# MMC_2_2_PSU.net
KiCad netlist of a schematic drawn in Altium Designer
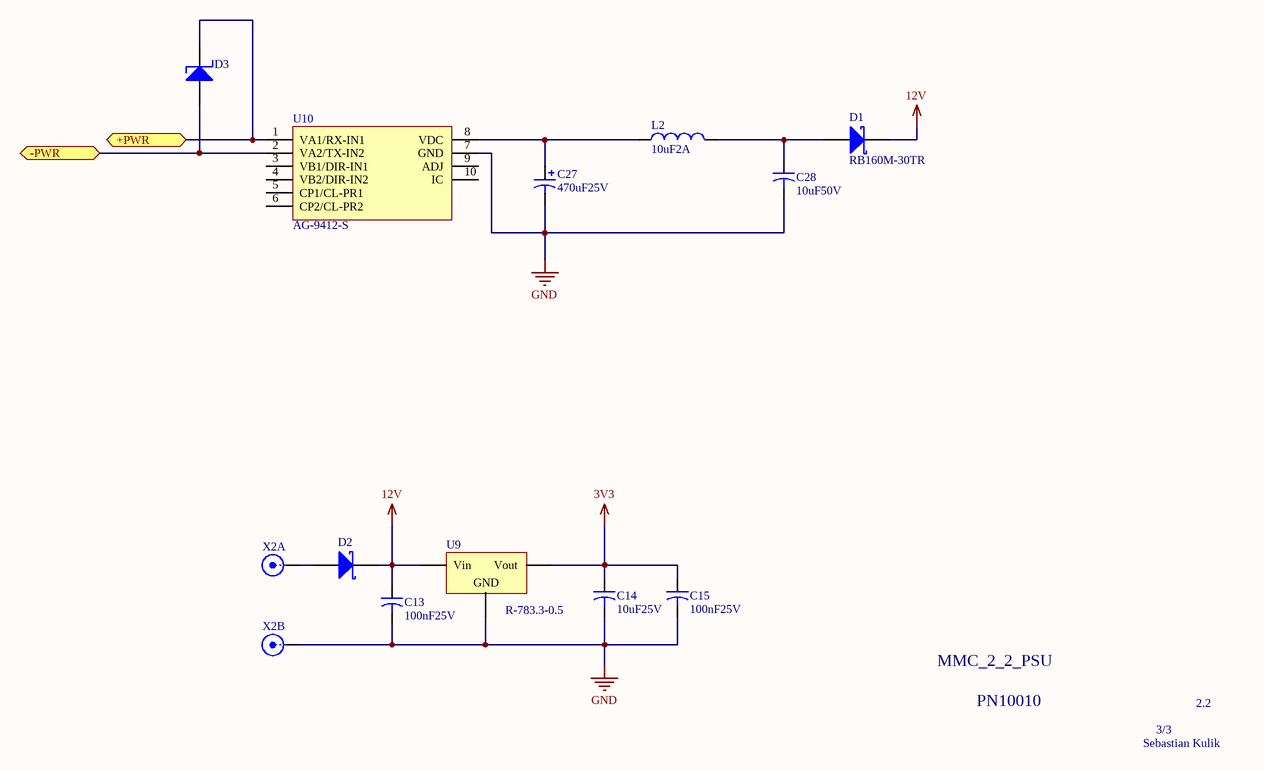
[diagram p0: MMC_2_2_PSU.SchDoc]

(export (version "E")
  (design (tool "Eeschema 10.0.6"))
  (components
    (comp (ref "C13")
      (value "100nF25V")
      (footprint "C0402")
      (description "AVX, X5R, 10%, 25V")
      (fields
        (field (name "MANUFACTURER") "AVX")
        (field (name "Comment") "100nF25V_0402")
        (field (name "PUBLISHER") "Sebastian Kulik")
      )
      (libsource (lib "Capacitors") (part "100nF25V_0402"))
    )
    (comp (ref "C14")
      (value "10uF25V")
      (footprint "C1210")
      (description "Capacitor")
      (fields
        (field (name "MANUFACTURER") "TDK")
        (field (name "Comment") "10uF25V_1210")
        (field (name "PUBLISHER") "Sebastian Kulik")
      )
      (libsource (lib "Capacitors") (part "10uF25V_1210"))
    )
    (comp (ref "C15")
      (value "100nF25V")
      (footprint "C0402")
      (description "AVX, X5R, 10%, 25V")
      (fields
        (field (name "MANUFACTURER") "AVX")
        (field (name "Comment") "100nF25V_0402")
        (field (name "PUBLISHER") "Sebastian Kulik")
      )
      (libsource (lib "Capacitors") (part "100nF25V_0402"))
    )
    (comp (ref "C27")
      (value "470uF25V")
      (footprint "Panasonic-H13")
      (description "Panasonic, TG series")
      (fields
        (field (name "MANUFACTURER") "Panasonic")
        (field (name "Comment") "470uF25V_POL")
        (field (name "PUBLISHER") "Sebastian Kulik")
      )
      (libsource (lib "Capacitors") (part "470uF25V_POL"))
    )
    (comp (ref "C28")
      (value "10uF50V")
      (footprint "C1210")
      (description "AVX,  X7R, 10%, 50V")
      (fields
        (field (name "MANUFACTURER") "AVX")
        (field (name "Comment") "10uF50V_1210")
        (field (name "PUBLISHER") "Sebastian Kulik")
      )
      (libsource (lib "Capacitors") (part "10uF50V_1210"))
    )
    (comp (ref "D1")
      (value "RB160M-30TR")
      (footprint "SOD123")
      (description "Diode Schottky,2A,40V")
      (fields (field (name "MANUFACTURER") "Rohm") (field (name "PUBLISHER") "Sebastian Kulik"))
      (libsource (lib "Discrete") (part "RB160M-30TR"))
    )
    (comp (ref "D2")
      (value "SD103AW-V-GS08")
      (footprint "SOD123")
      (description "Diode Schottky,2A,40V")
      (fields (field (name "MANUFACTURER") "Vishay") (field (name "PUBLISHER") "Sebastian Kulik"))
      (libsource (lib "Discrete") (part "SD103AW-V-GS08"))
    )
    (comp (ref "D3")
      (value "SMAJ58A-E3/61")
      (footprint "DO214A")
      (description "TVS, 400W, 58V")
      (fields (field (name "MANUFACTURER") "Vishay") (field (name "PUBLISHER") "Sebastian Kulik"))
      (libsource (lib "Discrete") (part "SMAJ58A-E3/61"))
    )
    (comp (ref "L2")
      (value "10uF2A")
      (footprint "WE-PD2_1")
      (description "WE-PD2, 10uF2A")
      (fields (field (name "MANUFACTURER") "WE") (field (name "PUBLISHER") "Sebastian Kulik"))
      (libsource (lib "Passives") (part "10uF2A_WE-PD2"))
    )
    (comp (ref "U9")
      (value "R-783.3-0.5")
      (footprint "R-783_3-0_5")
      (description "Voltage Regulator")
      (fields (field (name "MANUFACTURER") "Recom") (field (name "PUBLISHER") "Sebastian Kulik"))
      (libsource (lib "ICs") (part "Recom-R-783_3-0_5"))
    )
    (comp (ref "U10")
      (value "AG-9412-S")
      (footprint "AG-9412-S-1")
      (description "PoE, 12V")
      (fields (field (name "MANUFACTURER") "Silvertel") (field (name "PUBLISHER") "Sebastian Kulik"))
      (libsource (lib "ICs") (part "AG-9412-S"))
    )
    (comp (ref "X2")
      (value "PhoenixMSTBA-2")
      (footprint "MSTBA 2,5_2-G-5,08-LR")
      (fields (field (name "MANUFACTURER") "Phoenix Contact") (field (name "PUBLISHER") "Sebastian Kulik"))
      (libsource (lib "Connectors") (part "PhoenixMSTBA-2"))
    )
  )
  (nets
    (net (code "1") (name "/+PWR") (class "Default")
      (node (ref "D3") (pin "1") (pinfunction "K_1") (pintype "passive"))
      (node (ref "U10") (pin "1") (pinfunction "VA1/RX-IN1_1") (pintype "passive"))
    )
    (net (code "2") (name "/-PWR") (class "Default")
      (node (ref "D3") (pin "2") (pinfunction "A_2") (pintype "passive"))
      (node (ref "U10") (pin "2") (pinfunction "VA2/TX-IN2_2") (pintype "passive"))
    )
    (net (code "3") (name "3V3") (class "Default")
      (node (ref "C14") (pin "1") (pinfunction "1_1") (pintype "passive"))
      (node (ref "C15") (pin "1") (pinfunction "1_1") (pintype "passive"))
      (node (ref "U9") (pin "3") (pinfunction "Vout_3") (pintype "passive"))
    )
    (net (code "4") (name "12V") (class "Default")
      (node (ref "C13") (pin "1") (pinfunction "1_1") (pintype "passive"))
      (node (ref "D1") (pin "1") (pinfunction "K_1") (pintype "passive"))
      (node (ref "D2") (pin "1") (pinfunction "K_1") (pintype "passive"))
      (node (ref "U9") (pin "1") (pinfunction "Vin_1") (pintype "passive"))
    )
    (net (code "5") (name "GND") (class "Default")
      (node (ref "C13") (pin "2") (pinfunction "2_2") (pintype "passive"))
      (node (ref "C14") (pin "2") (pinfunction "2_2") (pintype "passive"))
      (node (ref "C15") (pin "2") (pinfunction "2_2") (pintype "passive"))
      (node (ref "C27") (pin "2") (pinfunction "2_2") (pintype "passive"))
      (node (ref "C28") (pin "2") (pinfunction "2_2") (pintype "passive"))
      (node (ref "U10") (pin "7") (pinfunction "GND_7") (pintype "passive"))
      (node (ref "U9") (pin "2") (pinfunction "GND_2") (pintype "passive"))
      (node (ref "X2") (pin "2") (pinfunction "Y_2") (pintype "passive"))
    )
    (net (code "6") (name "Net-(D1-A)") (class "Default")
      (node (ref "C28") (pin "1") (pinfunction "1_1") (pintype "passive"))
      (node (ref "D1") (pin "2") (pinfunction "A_2") (pintype "passive"))
      (node (ref "L2") (pin "2") (pinfunction "2_2") (pintype "passive"))
    )
    (net (code "7") (name "Net-(D2-A)") (class "Default")
      (node (ref "D2") (pin "2") (pinfunction "A_2") (pintype "passive"))
      (node (ref "X2") (pin "1") (pinfunction "X_1") (pintype "passive"))
    )
    (net (code "8") (name "Net-(U10-VDC)") (class "Default")
      (node (ref "C27") (pin "1") (pinfunction "1_1") (pintype "passive"))
      (node (ref "L2") (pin "1") (pinfunction "1_1") (pintype "passive"))
      (node (ref "U10") (pin "8") (pinfunction "VDC_8") (pintype "power_in"))
    )
    (net (code "9") (name "unconnected-(U10-ADJ-Pad9)") (class "Default")
      (node (ref "U10") (pin "9") (pinfunction "ADJ_9") (pintype "passive"))
    )
    (net (code "10") (name "unconnected-(U10-CP1{slash}CL-PR1-Pad5)") (class "Default")
      (node (ref "U10") (pin "5") (pinfunction "CP1/CL-PR1_5") (pintype "passive"))
    )
    (net (code "11") (name "unconnected-(U10-CP2{slash}CL-PR2-Pad6)") (class "Default")
      (node (ref "U10") (pin "6") (pinfunction "CP2/CL-PR2_6") (pintype "passive"))
    )
    (net (code "12") (name "unconnected-(U10-IC-Pad10)") (class "Default")
      (node (ref "U10") (pin "10") (pinfunction "IC_10") (pintype "passive"))
    )
    (net (code "13") (name "unconnected-(U10-VB1{slash}DIR-IN1-Pad3)") (class "Default")
      (node (ref "U10") (pin "3") (pinfunction "VB1/DIR-IN1_3") (pintype "passive"))
    )
    (net (code "14") (name "unconnected-(U10-VB2{slash}DIR-IN2-Pad4)") (class "Default")
      (node (ref "U10") (pin "4") (pinfunction "VB2/DIR-IN2_4") (pintype "passive"))
    )
  )
)
